# Peripherals_Main_Board.net
KiCad netlist of a schematic drawn in Altium Designer
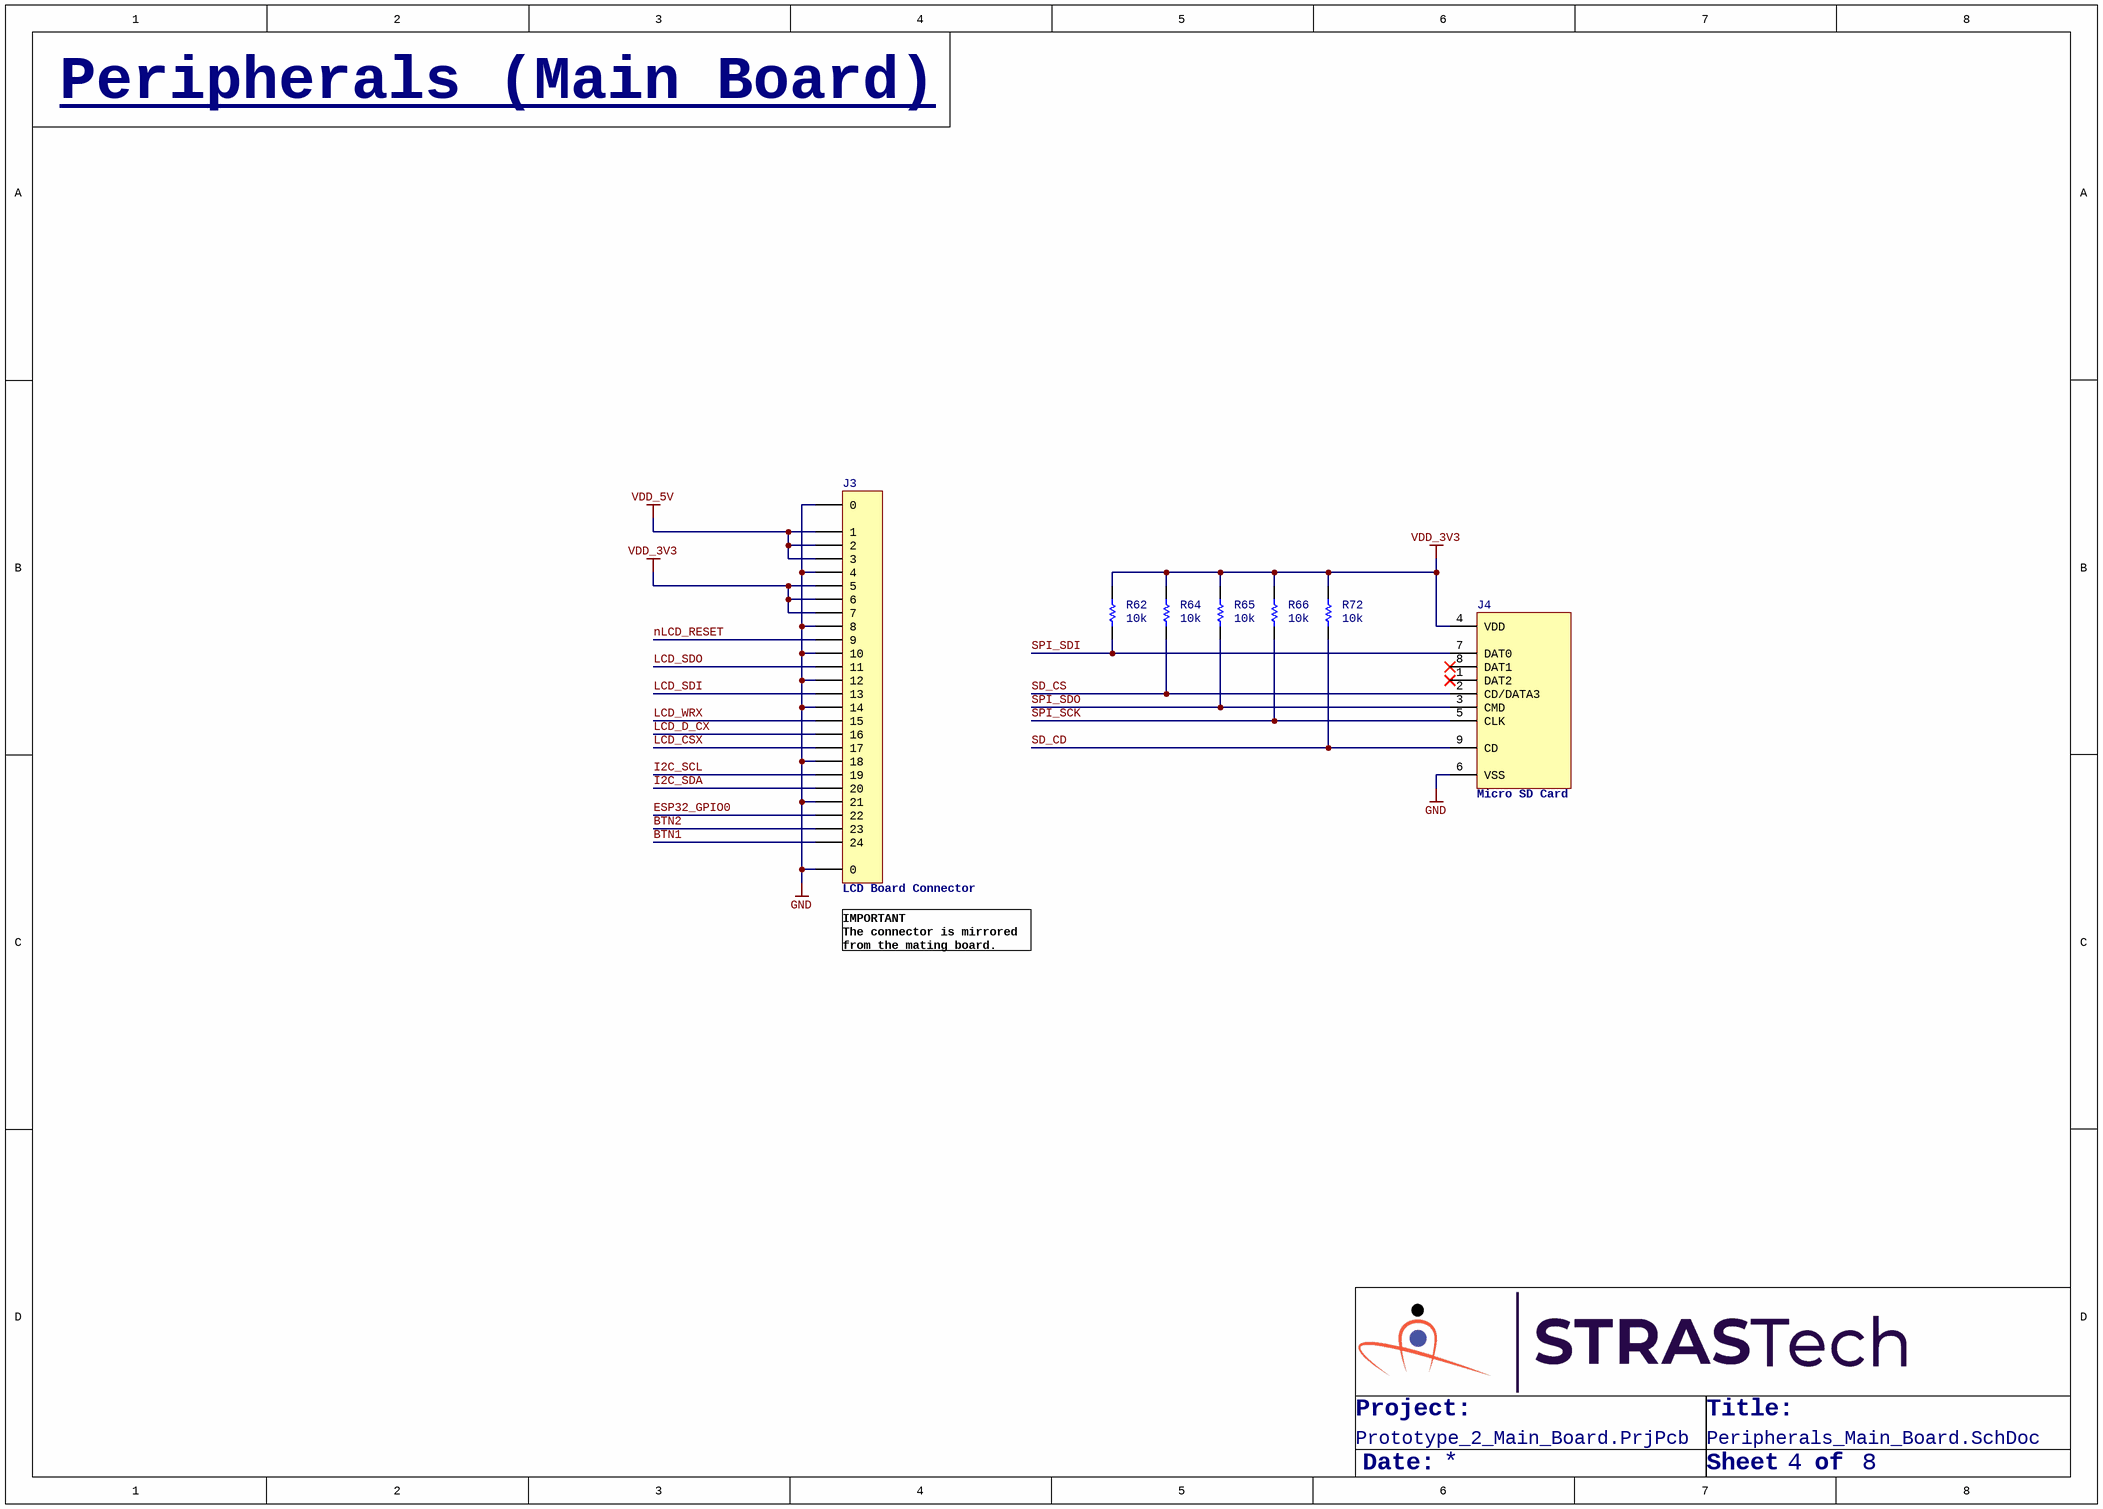
[diagram p0: Peripherals_Main_Board.SchDoc]

(export (version "E")
  (design (tool "Eeschema 10.0.6"))
  (components
    (comp (ref "J3")
      (value "Conn,FFC,Bottom,24 Pin,0.5mm")
      (footprint "Conn,FFC,Bottom,24Pos,0.5mm")
      (description "24 Position FFC, FPC Connector Contacts, Bottom 0.020\" (0.50mm) Surface Mount, Right Angle")
      (fields
        (field (name "VENDOR PART NUMBER") "2057-PCA-6-LA-24-HL-3-ND")
        (field (name "MANUFACTURER") "Adam Tech")
        (field (name "CREATED BY") "Judd Foster")
      )
      (libsource (lib "symbols") (part "Conn,FFC,Bottom,24 Pin,0.5mm"))
    )
    (comp (ref "J4")
      (value "Micro SD Card")
      (footprint "Conn,MicroSD,Push-Push,SMD")
      (description "9 (8 + 1) Position Card Connector Secure Digital - microSD™ Surface Mount, Right Angle Gold")
      (fields
        (field (name "MANUFACTURER") "GCT")
        (field (name "MANUFACTURER PART NUMBER") "MEM2075-00-140-01-A")
        (field (name "CREATEDBY") "Judd Foster")
      )
      (libsource (lib "symbols") (part "Conn,MicroSD,SMD,Push-Push"))
    )
    (comp (ref "R62")
      (value "10k")
      (footprint "RES,0402")
      (description "10 kOhms ±5% 0.063W, 1/16W Chip Resistor 0402 (1005 Metric) Automotive AEC-Q200 Thick Film")
      (fields
        (field (name "VENDOR PART NUMBER") "RMCF0402JT10K0CT-ND")
        (field (name "MANUFACTURER") "Stackpole Electronics Inc")
        (field (name "CREATEDBY") "Judd Foster")
      )
      (libsource (lib "symbols") (part "RES,10k,5%,0.063W,0402"))
    )
    (comp (ref "R64")
      (value "10k")
      (footprint "RES,0402")
      (description "10 kOhms ±5% 0.063W, 1/16W Chip Resistor 0402 (1005 Metric) Automotive AEC-Q200 Thick Film")
      (fields
        (field (name "VENDOR PART NUMBER") "RMCF0402JT10K0CT-ND")
        (field (name "MANUFACTURER") "Stackpole Electronics Inc")
        (field (name "CREATEDBY") "Judd Foster")
      )
      (libsource (lib "symbols") (part "RES,10k,5%,0.063W,0402"))
    )
    (comp (ref "R65")
      (value "10k")
      (footprint "RES,0402")
      (description "10 kOhms ±5% 0.063W, 1/16W Chip Resistor 0402 (1005 Metric) Automotive AEC-Q200 Thick Film")
      (fields
        (field (name "VENDOR PART NUMBER") "RMCF0402JT10K0CT-ND")
        (field (name "MANUFACTURER") "Stackpole Electronics Inc")
        (field (name "CREATEDBY") "Judd Foster")
      )
      (libsource (lib "symbols") (part "RES,10k,5%,0.063W,0402"))
    )
    (comp (ref "R66")
      (value "10k")
      (footprint "RES,0402")
      (description "10 kOhms ±5% 0.063W, 1/16W Chip Resistor 0402 (1005 Metric) Automotive AEC-Q200 Thick Film")
      (fields
        (field (name "VENDOR PART NUMBER") "RMCF0402JT10K0CT-ND")
        (field (name "MANUFACTURER") "Stackpole Electronics Inc")
        (field (name "CREATEDBY") "Judd Foster")
      )
      (libsource (lib "symbols") (part "RES,10k,5%,0.063W,0402"))
    )
    (comp (ref "R72")
      (value "10k")
      (footprint "RES,0402")
      (description "10 kOhms ±5% 0.063W, 1/16W Chip Resistor 0402 (1005 Metric) Automotive AEC-Q200 Thick Film")
      (fields
        (field (name "VENDOR PART NUMBER") "RMCF0402JT10K0CT-ND")
        (field (name "MANUFACTURER") "Stackpole Electronics Inc")
        (field (name "CREATEDBY") "Judd Foster")
      )
      (libsource (lib "symbols") (part "RES,10k,5%,0.063W,0402"))
    )
  )
  (nets
    (net (code "1") (name "/BTN1") (class "Default")
      (node (ref "J3") (pin "24") (pinfunction "24_24") (pintype "passive"))
    )
    (net (code "2") (name "/BTN2") (class "Default")
      (node (ref "J3") (pin "23") (pinfunction "23_23") (pintype "passive"))
    )
    (net (code "3") (name "/ESP32_GPIO0") (class "Default")
      (node (ref "J3") (pin "22") (pinfunction "22_22") (pintype "passive"))
    )
    (net (code "4") (name "/I2C_SCL") (class "Default")
      (node (ref "J3") (pin "19") (pinfunction "19_19") (pintype "passive"))
    )
    (net (code "5") (name "/I2C_SDA") (class "Default")
      (node (ref "J3") (pin "20") (pinfunction "20_20") (pintype "passive"))
    )
    (net (code "6") (name "/LCD_CSX") (class "Default")
      (node (ref "J3") (pin "17") (pinfunction "17_17") (pintype "passive"))
    )
    (net (code "7") (name "/LCD_D_CX") (class "Default")
      (node (ref "J3") (pin "16") (pinfunction "16_16") (pintype "passive"))
    )
    (net (code "8") (name "/LCD_SDI") (class "Default")
      (node (ref "J3") (pin "13") (pinfunction "13_13") (pintype "passive"))
    )
    (net (code "9") (name "/LCD_SDO") (class "Default")
      (node (ref "J3") (pin "11") (pinfunction "11_11") (pintype "passive"))
    )
    (net (code "10") (name "/LCD_WRX") (class "Default")
      (node (ref "J3") (pin "15") (pinfunction "15_15") (pintype "passive"))
    )
    (net (code "11") (name "/SD_CD") (class "Default")
      (node (ref "J4") (pin "9") (pinfunction "CD_9") (pintype "passive"))
      (node (ref "R72") (pin "1") (pinfunction "1_1") (pintype "passive"))
    )
    (net (code "12") (name "/SD_CS") (class "Default")
      (node (ref "J4") (pin "2") (pinfunction "CD/DATA3_2") (pintype "passive"))
      (node (ref "R64") (pin "1") (pinfunction "1_1") (pintype "passive"))
    )
    (net (code "13") (name "/SPI_SCK") (class "Default")
      (node (ref "J4") (pin "5") (pinfunction "CLK_5") (pintype "passive"))
      (node (ref "R66") (pin "1") (pinfunction "1_1") (pintype "passive"))
    )
    (net (code "14") (name "/SPI_SDI") (class "Default")
      (node (ref "J4") (pin "7") (pinfunction "DAT0_7") (pintype "passive"))
      (node (ref "R62") (pin "1") (pinfunction "1_1") (pintype "passive"))
    )
    (net (code "15") (name "/SPI_SDO") (class "Default")
      (node (ref "J4") (pin "3") (pinfunction "CMD_3") (pintype "passive"))
      (node (ref "R65") (pin "1") (pinfunction "1_1") (pintype "passive"))
    )
    (net (code "16") (name "/nLCD_RESET") (class "Default")
      (node (ref "J3") (pin "9") (pinfunction "9_9") (pintype "passive"))
    )
    (net (code "17") (name "GND") (class "Default")
      (node (ref "J3") (pin "0") (pinfunction "0_0") (pintype "passive"))
      (node (ref "J3") (pin "10") (pinfunction "10_10") (pintype "passive"))
      (node (ref "J3") (pin "12") (pinfunction "12_12") (pintype "passive"))
      (node (ref "J3") (pin "14") (pinfunction "14_14") (pintype "passive"))
      (node (ref "J3") (pin "18") (pinfunction "18_18") (pintype "passive"))
      (node (ref "J3") (pin "21") (pinfunction "21_21") (pintype "passive"))
      (node (ref "J3") (pin "4") (pinfunction "4_4") (pintype "passive"))
      (node (ref "J3") (pin "8") (pinfunction "8_8") (pintype "passive"))
      (node (ref "J4") (pin "6") (pinfunction "VSS_6") (pintype "passive"))
    )
    (net (code "18") (name "VDD_3V3") (class "Default")
      (node (ref "J3") (pin "5") (pinfunction "5_5") (pintype "passive"))
      (node (ref "J3") (pin "6") (pinfunction "6_6") (pintype "passive"))
      (node (ref "J3") (pin "7") (pinfunction "7_7") (pintype "passive"))
      (node (ref "J4") (pin "4") (pinfunction "VDD_4") (pintype "passive"))
      (node (ref "R62") (pin "2") (pinfunction "2_2") (pintype "passive"))
      (node (ref "R64") (pin "2") (pinfunction "2_2") (pintype "passive"))
      (node (ref "R65") (pin "2") (pinfunction "2_2") (pintype "passive"))
      (node (ref "R66") (pin "2") (pinfunction "2_2") (pintype "passive"))
      (node (ref "R72") (pin "2") (pinfunction "2_2") (pintype "passive"))
    )
    (net (code "19") (name "VDD_5V") (class "Default")
      (node (ref "J3") (pin "1") (pinfunction "1_1") (pintype "passive"))
      (node (ref "J3") (pin "2") (pinfunction "2_2") (pintype "passive"))
      (node (ref "J3") (pin "3") (pinfunction "3_3") (pintype "passive"))
    )
    (net (code "20") (name "unconnected-(J4-DAT1-Pad8)") (class "Default")
      (node (ref "J4") (pin "8") (pinfunction "DAT1_8") (pintype "passive+no_connect"))
    )
    (net (code "21") (name "unconnected-(J4-DAT2-Pad1)") (class "Default")
      (node (ref "J4") (pin "1") (pinfunction "DAT2_1") (pintype "passive+no_connect"))
    )
  )
)
